# Schematics.net
KiCad netlist of a schematic drawn in EAGLE
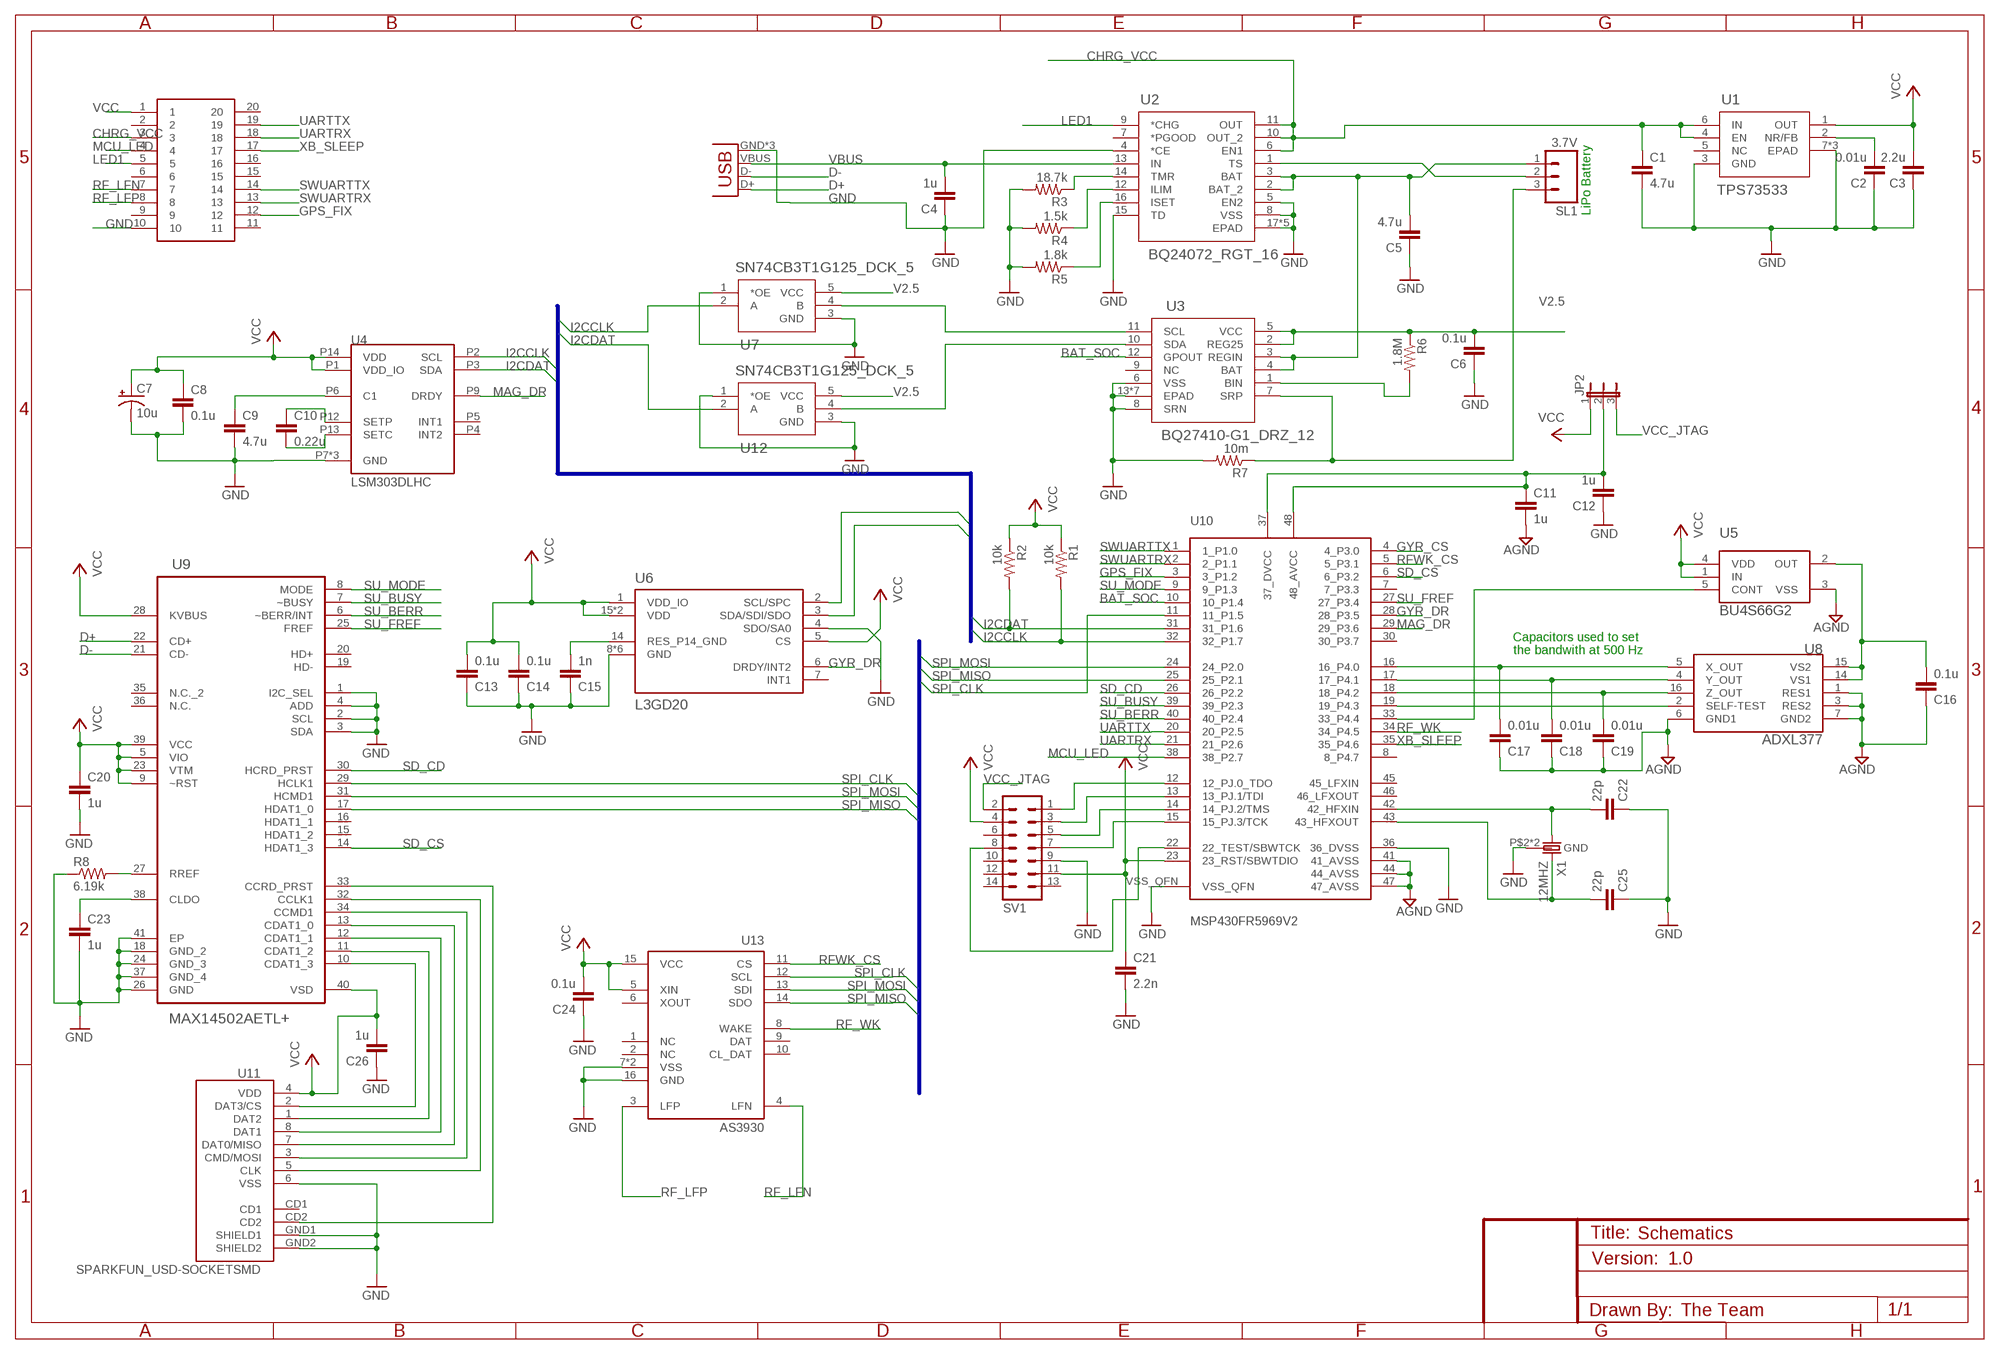
[diagram p0: schematic, sheet 1]

(export (version "E")
  (design (tool "Eeschema 10.0.6"))
  (components
    (comp (ref "C1")
      (value "4.7u")
      (footprint "eagle-import:C0603")
      (libsource (lib "eagle-import") (part "C-EUC0603"))
    )
    (comp (ref "C2")
      (value "0.01u")
      (footprint "eagle-import:C0603")
      (libsource (lib "eagle-import") (part "C-EUC0603"))
    )
    (comp (ref "C3")
      (value "2.2u")
      (footprint "eagle-import:C0603")
      (libsource (lib "eagle-import") (part "C-EUC0603"))
    )
    (comp (ref "C4")
      (value "1u")
      (footprint "eagle-import:C0603")
      (libsource (lib "eagle-import") (part "C-EUC0603"))
    )
    (comp (ref "C5")
      (value "4.7u")
      (footprint "eagle-import:C0603")
      (libsource (lib "eagle-import") (part "C-EUC0603"))
    )
    (comp (ref "C6")
      (value "0.1u")
      (footprint "eagle-import:C0603")
      (libsource (lib "eagle-import") (part "C-EUC0603"))
    )
    (comp (ref "C7")
      (value "10u")
      (footprint "eagle-import:ELECTROLYTIC_CAP")
      (libsource (lib "eagle-import") (part "SMD-AL-CAP"))
    )
    (comp (ref "C8")
      (value "0.1u")
      (footprint "eagle-import:C0603")
      (libsource (lib "eagle-import") (part "C-EUC0603"))
    )
    (comp (ref "C9")
      (value "4.7u")
      (footprint "eagle-import:C0603")
      (libsource (lib "eagle-import") (part "C-EUC0603"))
    )
    (comp (ref "C10")
      (value "0.22u")
      (footprint "eagle-import:C0603")
      (libsource (lib "eagle-import") (part "C-EUC0603"))
    )
    (comp (ref "C11")
      (value "1u")
      (footprint "eagle-import:C0603")
      (libsource (lib "eagle-import") (part "C-EUC0603"))
    )
    (comp (ref "C12")
      (value "1u")
      (footprint "eagle-import:C0603")
      (libsource (lib "eagle-import") (part "C-EUC0603"))
    )
    (comp (ref "C13")
      (value "0.1u")
      (footprint "eagle-import:C0603")
      (libsource (lib "eagle-import") (part "C-EUC0603"))
    )
    (comp (ref "C14")
      (value "0.1u")
      (footprint "eagle-import:C0603")
      (libsource (lib "eagle-import") (part "C-EUC0603"))
    )
    (comp (ref "C15")
      (value "1n")
      (footprint "eagle-import:C0603")
      (libsource (lib "eagle-import") (part "C-EUC0603"))
    )
    (comp (ref "C16")
      (value "0.1u")
      (footprint "eagle-import:C0603")
      (libsource (lib "eagle-import") (part "C-EUC0603"))
    )
    (comp (ref "C17")
      (value "0.01u")
      (footprint "eagle-import:C0603")
      (libsource (lib "eagle-import") (part "C-EUC0603"))
    )
    (comp (ref "C18")
      (value "0.01u")
      (footprint "eagle-import:C0603")
      (libsource (lib "eagle-import") (part "C-EUC0603"))
    )
    (comp (ref "C19")
      (value "0.01u")
      (footprint "eagle-import:C0603")
      (libsource (lib "eagle-import") (part "C-EUC0603"))
    )
    (comp (ref "C20")
      (value "1u")
      (footprint "eagle-import:C0603")
      (libsource (lib "eagle-import") (part "C-EUC0603"))
    )
    (comp (ref "C21")
      (value "2.2n")
      (footprint "eagle-import:C0603")
      (libsource (lib "eagle-import") (part "C-EUC0603"))
    )
    (comp (ref "C22")
      (value "22p")
      (footprint "eagle-import:C0603")
      (libsource (lib "eagle-import") (part "C-EUC0603"))
    )
    (comp (ref "C23")
      (value "1u")
      (footprint "eagle-import:C0603")
      (libsource (lib "eagle-import") (part "C-EUC0603"))
    )
    (comp (ref "C24")
      (value "0.1u")
      (footprint "eagle-import:C0603")
      (libsource (lib "eagle-import") (part "C-EUC0603"))
    )
    (comp (ref "C25")
      (value "22p")
      (footprint "eagle-import:C0603")
      (libsource (lib "eagle-import") (part "C-EUC0603"))
    )
    (comp (ref "C26")
      (value "1u")
      (footprint "eagle-import:C0603")
      (libsource (lib "eagle-import") (part "C-EUC0603"))
    )
    (comp (ref "JP1")
      (value "USB-MICROB")
      (footprint "eagle-import:USB-MICROB")
      (libsource (lib "eagle-import") (part "USB-MICROB"))
    )
    (comp (ref "JP2")
      (value "JP2E")
      (footprint "eagle-import:JP2")
      (libsource (lib "eagle-import") (part "JP2E"))
    )
    (comp (ref "JP3")
      (value "20-SOCKET")
      (footprint "eagle-import:20-SOCKET")
      (libsource (lib "eagle-import") (part "20-SOCKET"))
    )
    (comp (ref "R1")
      (value "10k")
      (footprint "eagle-import:R0603")
      (libsource (lib "eagle-import") (part "R-US_R0603"))
    )
    (comp (ref "R2")
      (value "10k")
      (footprint "eagle-import:R0603")
      (libsource (lib "eagle-import") (part "R-US_R0603"))
    )
    (comp (ref "R3")
      (value "18.7k")
      (footprint "eagle-import:R0603")
      (libsource (lib "eagle-import") (part "R-US_R0603"))
    )
    (comp (ref "R4")
      (value "1.5k")
      (footprint "eagle-import:R0603")
      (libsource (lib "eagle-import") (part "R-US_R0603"))
    )
    (comp (ref "R5")
      (value "1.8k")
      (footprint "eagle-import:R0603")
      (libsource (lib "eagle-import") (part "R-US_R0603"))
    )
    (comp (ref "R6")
      (value "1.8M")
      (footprint "eagle-import:R0603")
      (libsource (lib "eagle-import") (part "R-US_R0603"))
    )
    (comp (ref "R7")
      (value "10m")
      (footprint "eagle-import:R0603")
      (libsource (lib "eagle-import") (part "R-US_R0603"))
    )
    (comp (ref "R8")
      (value "6.19k")
      (footprint "eagle-import:R0603")
      (libsource (lib "eagle-import") (part "R-US_R0603"))
    )
    (comp (ref "SL1")
      (value "3.7V")
      (footprint "eagle-import:03P")
      (libsource (lib "eagle-import") (part "M03"))
    )
    (comp (ref "SV1")
      (value "ML14")
      (footprint "eagle-import:ML14")
      (libsource (lib "eagle-import") (part "ML14"))
    )
    (comp (ref "U1")
      (value "TPS73533")
      (footprint "eagle-import:DRV6_1P6X1")
      (fields
        (field (name "MANUFACTURER") "Texas Instruments")
        (field (name "MANUFACTURER_PART_NUMBER") "tps73533_drv_6")
      )
      (libsource (lib "eagle-import") (part "TPS73533_DRV_6"))
    )
    (comp (ref "U2")
      (value "BQ24072_RGT_16")
      (footprint "eagle-import:RGT16_1P7X1P7")
      (fields
        (field (name "GENERIC_PART_NUMBER") "BQ24072")
        (field (name "MANUFACTURER") "Texas Instruments")
      )
      (libsource (lib "eagle-import") (part "BQ24072_RGT_16"))
    )
    (comp (ref "U3")
      (value "BQ27410-G1_DRZ_12")
      (footprint "eagle-import:DRZ12_1P95X2P45")
      (fields
        (field (name "GENERIC_PART_NUMBER") "BQ27410-G1")
        (field (name "MANUFACTURER") "Texas Instruments")
      )
      (libsource (lib "eagle-import") (part "BQ27410-G1_DRZ_12"))
    )
    (comp (ref "U4")
      (value "LSM303DLHC")
      (footprint "eagle-import:LGA_3X5X1_14L")
      (libsource (lib "eagle-import") (part "LSM303DLHC"))
    )
    (comp (ref "U5")
      (value "BU4S66G2")
      (footprint "eagle-import:SSOP5")
      (libsource (lib "eagle-import") (part "BU4S66G2"))
    )
    (comp (ref "U6")
      (value "L3GD20")
      (footprint "eagle-import:L3GD20")
      (libsource (lib "eagle-import") (part "L3GD20"))
    )
    (comp (ref "U7")
      (value "SN74CB3T1G125_DCK_5")
      (footprint "eagle-import:DCK5")
      (fields
        (field (name "GENERIC_PART_NUMBER") "SN74CB3T1G125")
        (field (name "MANUFACTURER") "Texas Instruments")
        (field (name "MANUFACTURER_PART_NUMBER") "sn74cb3t1g125_dck_5")
      )
      (libsource (lib "eagle-import") (part "SN74CB3T1G125_DCK_5"))
    )
    (comp (ref "U8")
      (value "ADXL377")
      (footprint "eagle-import:LFCSP-16")
      (libsource (lib "eagle-import") (part "ADXL377"))
    )
    (comp (ref "U9")
      (value "MAX14502AETL+")
      (footprint "eagle-import:QFN40P500X500X80-41N")
      (libsource (lib "eagle-import") (part "MAX14502AETL+"))
    )
    (comp (ref "U10")
      (value "MSP430FR5969V2")
      (footprint "eagle-import:RGZ(S-PVQFN-N48)")
      (libsource (lib "eagle-import") (part "MSP430FR5969V2"))
    )
    (comp (ref "U11")
      (value "SPARKFUN_USD-SOCKETSMD")
      (footprint "eagle-import:SPARKFUN_MICRO-SD-SOCKET-PP")
      (libsource (lib "eagle-import") (part "SPARKFUN_USD-SOCKETSMD"))
    )
    (comp (ref "U12")
      (value "SN74CB3T1G125_DCK_5")
      (footprint "eagle-import:DCK5")
      (fields
        (field (name "GENERIC_PART_NUMBER") "SN74CB3T1G125")
        (field (name "MANUFACTURER") "Texas Instruments")
        (field (name "MANUFACTURER_PART_NUMBER") "sn74cb3t1g125_dck_5")
      )
      (libsource (lib "eagle-import") (part "SN74CB3T1G125_DCK_5"))
    )
    (comp (ref "U13")
      (value "AS3930")
      (footprint "eagle-import:AS3930")
      (libsource (lib "eagle-import") (part "AS3930"))
    )
    (comp (ref "X1")
      (value "12MHZ")
      (footprint "eagle-import:12MHZ")
      (libsource (lib "eagle-import") (part "12MHZ"))
    )
  )
  (nets
    (net (code "1") (name "/BAT_SOC") (class "Default")
      (node (ref "U10") (pin "10") (pinfunction "10_P1.4_10") (pintype "bidirectional"))
      (node (ref "U3") (pin "12") (pinfunction "GPOUT_12") (pintype "output"))
    )
    (net (code "2") (name "/CHRG_VCC") (class "Default")
      (node (ref "C1") (pin "1") (pinfunction "1_1") (pintype "passive"))
      (node (ref "JP3") (pin "3") (pinfunction "3_3") (pintype "bidirectional"))
      (node (ref "U1") (pin "4") (pinfunction "EN_4") (pintype "passive"))
      (node (ref "U1") (pin "6") (pinfunction "IN_6") (pintype "input"))
      (node (ref "U2") (pin "10") (pinfunction "OUT_2_10") (pintype "output"))
      (node (ref "U2") (pin "11") (pinfunction "OUT_11") (pintype "output"))
      (node (ref "U2") (pin "6") (pinfunction "EN1_6") (pintype "input"))
    )
    (net (code "3") (name "/D+") (class "Default")
      (node (ref "JP1") (pin "D+") (pinfunction "D+_D+") (pintype "bidirectional"))
      (node (ref "U9") (pin "22") (pinfunction "CD+_22") (pintype "passive"))
    )
    (net (code "4") (name "/D-") (class "Default")
      (node (ref "JP1") (pin "D-") (pinfunction "D-_D-") (pintype "bidirectional"))
      (node (ref "U9") (pin "21") (pinfunction "CD-_21") (pintype "passive"))
    )
    (net (code "5") (name "/GPS_FIX") (class "Default")
      (node (ref "JP3") (pin "12") (pinfunction "12_12") (pintype "bidirectional"))
      (node (ref "U10") (pin "3") (pinfunction "3_P1.2_3") (pintype "bidirectional"))
    )
    (net (code "6") (name "/GYR_CS") (class "Default")
      (node (ref "U10") (pin "4") (pinfunction "4_P3.0_4") (pintype "bidirectional"))
    )
    (net (code "7") (name "/GYR_DR") (class "Default")
      (node (ref "U10") (pin "28") (pinfunction "28_P3.5_28") (pintype "bidirectional"))
      (node (ref "U6") (pin "6") (pinfunction "DRDY/INT2_6") (pintype "output"))
    )
    (net (code "8") (name "/I2CCLK") (class "Default")
      (node (ref "R1") (pin "2") (pinfunction "2_2") (pintype "passive"))
      (node (ref "U10") (pin "32") (pinfunction "32_P1.7_32") (pintype "bidirectional"))
      (node (ref "U4") (pin "P2") (pinfunction "SCL_P2") (pintype "bidirectional"))
      (node (ref "U6") (pin "2") (pinfunction "SCL/SPC_2") (pintype "input"))
      (node (ref "U7") (pin "2") (pinfunction "A_2") (pintype "input"))
    )
    (net (code "9") (name "/I2CDAT") (class "Default")
      (node (ref "R2") (pin "2") (pinfunction "2_2") (pintype "passive"))
      (node (ref "U10") (pin "31") (pinfunction "31_P1.6_31") (pintype "bidirectional"))
      (node (ref "U12") (pin "2") (pinfunction "A_2") (pintype "input"))
      (node (ref "U4") (pin "P3") (pinfunction "SDA_P3") (pintype "bidirectional"))
      (node (ref "U6") (pin "3") (pinfunction "SDA/SDI/SDO_3") (pintype "bidirectional"))
    )
    (net (code "10") (name "/LED1") (class "Default")
      (node (ref "JP3") (pin "5") (pinfunction "5_5") (pintype "bidirectional"))
      (node (ref "U2") (pin "9") (pinfunction "*CHG_9") (pintype "output"))
    )
    (net (code "11") (name "/MAG_DR") (class "Default")
      (node (ref "U10") (pin "29") (pinfunction "29_P3.6_29") (pintype "bidirectional"))
      (node (ref "U4") (pin "P9") (pinfunction "DRDY_P9") (pintype "bidirectional"))
    )
    (net (code "12") (name "/MCU_LED") (class "Default")
      (node (ref "JP3") (pin "4") (pinfunction "4_4") (pintype "bidirectional"))
      (node (ref "U10") (pin "38") (pinfunction "38_P2.7_38") (pintype "bidirectional"))
    )
    (net (code "13") (name "/RFWK_CS") (class "Default")
      (node (ref "U10") (pin "5") (pinfunction "5_P3.1_5") (pintype "bidirectional"))
      (node (ref "U13") (pin "11") (pinfunction "CS_11") (pintype "bidirectional"))
    )
    (net (code "14") (name "/RF_LFN") (class "Default")
      (node (ref "JP3") (pin "7") (pinfunction "7_7") (pintype "bidirectional"))
      (node (ref "U13") (pin "4") (pinfunction "LFN_4") (pintype "bidirectional"))
    )
    (net (code "15") (name "/RF_LFP") (class "Default")
      (node (ref "JP3") (pin "8") (pinfunction "8_8") (pintype "bidirectional"))
      (node (ref "U13") (pin "3") (pinfunction "LFP_3") (pintype "bidirectional"))
    )
    (net (code "16") (name "/RF_WK") (class "Default")
      (node (ref "U10") (pin "34") (pinfunction "34_P4.5_34") (pintype "bidirectional"))
      (node (ref "U13") (pin "8") (pinfunction "WAKE_8") (pintype "bidirectional"))
    )
    (net (code "17") (name "/SD_CD") (class "Default")
      (node (ref "U10") (pin "26") (pinfunction "26_P2.2_26") (pintype "bidirectional"))
      (node (ref "U9") (pin "30") (pinfunction "HCRD_PRST_30") (pintype "passive"))
    )
    (net (code "18") (name "/SD_CS") (class "Default")
      (node (ref "U10") (pin "6") (pinfunction "6_P3.2_6") (pintype "bidirectional"))
      (node (ref "U9") (pin "14") (pinfunction "HDAT1_3_14") (pintype "passive"))
    )
    (net (code "19") (name "/SPI_CLK") (class "Default")
      (node (ref "U10") (pin "11") (pinfunction "11_P1.5_11") (pintype "bidirectional"))
      (node (ref "U13") (pin "12") (pinfunction "SCL_12") (pintype "bidirectional"))
      (node (ref "U9") (pin "29") (pinfunction "HCLK1_29") (pintype "input"))
    )
    (net (code "20") (name "/SPI_MISO") (class "Default")
      (node (ref "U10") (pin "25") (pinfunction "25_P2.1_25") (pintype "bidirectional"))
      (node (ref "U13") (pin "14") (pinfunction "SDO_14") (pintype "bidirectional"))
      (node (ref "U9") (pin "17") (pinfunction "HDAT1_0_17") (pintype "passive"))
    )
    (net (code "21") (name "/SPI_MOSI") (class "Default")
      (node (ref "U10") (pin "24") (pinfunction "24_P2.0_24") (pintype "bidirectional"))
      (node (ref "U13") (pin "13") (pinfunction "SDI_13") (pintype "bidirectional"))
      (node (ref "U9") (pin "31") (pinfunction "HCMD1_31") (pintype "passive"))
    )
    (net (code "22") (name "/SU_BERR") (class "Default")
      (node (ref "U10") (pin "40") (pinfunction "40_P2.4_40") (pintype "bidirectional"))
      (node (ref "U9") (pin "6") (pinfunction "~{BERR/INT}_6") (pintype "bidirectional"))
    )
    (net (code "23") (name "/SU_BUSY") (class "Default")
      (node (ref "U10") (pin "39") (pinfunction "39_P2.3_39") (pintype "bidirectional"))
      (node (ref "U9") (pin "7") (pinfunction "~{BUSY}_7") (pintype "output"))
    )
    (net (code "24") (name "/SU_FREF") (class "Default")
      (node (ref "U10") (pin "27") (pinfunction "27_P3.4_27") (pintype "bidirectional"))
      (node (ref "U9") (pin "25") (pinfunction "FREF_25") (pintype "passive"))
    )
    (net (code "25") (name "/SU_MODE") (class "Default")
      (node (ref "U10") (pin "9") (pinfunction "9_P1.3_9") (pintype "bidirectional"))
      (node (ref "U9") (pin "8") (pinfunction "MODE_8") (pintype "input"))
    )
    (net (code "26") (name "/SWUARTRX") (class "Default")
      (node (ref "JP3") (pin "13") (pinfunction "13_13") (pintype "bidirectional"))
      (node (ref "U10") (pin "2") (pinfunction "2_P1.1_2") (pintype "bidirectional"))
    )
    (net (code "27") (name "/SWUARTTX") (class "Default")
      (node (ref "JP3") (pin "14") (pinfunction "14_14") (pintype "bidirectional"))
      (node (ref "U10") (pin "1") (pinfunction "1_P1.0_1") (pintype "bidirectional"))
    )
    (net (code "28") (name "/UARTRX") (class "Default")
      (node (ref "JP3") (pin "18") (pinfunction "18_18") (pintype "bidirectional"))
      (node (ref "U10") (pin "21") (pinfunction "21_P2.6_21") (pintype "bidirectional"))
    )
    (net (code "29") (name "/UARTTX") (class "Default")
      (node (ref "JP3") (pin "19") (pinfunction "19_19") (pintype "bidirectional"))
      (node (ref "U10") (pin "20") (pinfunction "20_P2.5_20") (pintype "bidirectional"))
    )
    (net (code "30") (name "/V2.5") (class "Default")
      (node (ref "C6") (pin "2") (pinfunction "2_2") (pintype "passive"))
      (node (ref "R6") (pin "1") (pinfunction "1_1") (pintype "passive"))
      (node (ref "U12") (pin "5") (pinfunction "VCC_5") (pintype "power_in"))
      (node (ref "U3") (pin "2") (pinfunction "REG25_2") (pintype "power_in"))
      (node (ref "U3") (pin "5") (pinfunction "VCC_5") (pintype "power_in"))
      (node (ref "U7") (pin "5") (pinfunction "VCC_5") (pintype "power_in"))
    )
    (net (code "31") (name "/VBUS") (class "Default")
      (node (ref "C4") (pin "2") (pinfunction "2_2") (pintype "passive"))
      (node (ref "JP1") (pin "VBUS") (pinfunction "VBUS_VBUS") (pintype "bidirectional"))
      (node (ref "U2") (pin "13") (pinfunction "IN_13") (pintype "input"))
    )
    (net (code "32") (name "/VCC_JTAG") (class "Default")
      (node (ref "JP2") (pin "3") (pinfunction "3_3") (pintype "passive"))
      (node (ref "SV1") (pin "2") (pinfunction "2_2") (pintype "passive"))
    )
    (net (code "33") (name "/XB_SLEEP") (class "Default")
      (node (ref "JP3") (pin "17") (pinfunction "17_17") (pintype "bidirectional"))
      (node (ref "U10") (pin "35") (pinfunction "35_P4.6_35") (pintype "bidirectional"))
    )
    (net (code "34") (name "AGND") (class "Default")
      (node (ref "C11") (pin "2") (pinfunction "2_2") (pintype "passive"))
      (node (ref "C16") (pin "1") (pinfunction "1_1") (pintype "passive"))
      (node (ref "C17") (pin "1") (pinfunction "1_1") (pintype "passive"))
      (node (ref "C18") (pin "1") (pinfunction "1_1") (pintype "passive"))
      (node (ref "C19") (pin "1") (pinfunction "1_1") (pintype "passive"))
      (node (ref "U10") (pin "41") (pinfunction "41_AVSS_41") (pintype "bidirectional"))
      (node (ref "U10") (pin "44") (pinfunction "44_AVSS_44") (pintype "bidirectional"))
      (node (ref "U10") (pin "47") (pinfunction "47_AVSS_47") (pintype "bidirectional"))
      (node (ref "U5") (pin "3") (pinfunction "VSS_3") (pintype "bidirectional"))
      (node (ref "U8") (pin "1") (pinfunction "RES1_1") (pintype "bidirectional"))
      (node (ref "U8") (pin "3") (pinfunction "RES2_3") (pintype "bidirectional"))
      (node (ref "U8") (pin "6") (pinfunction "GND1_6") (pintype "bidirectional"))
      (node (ref "U8") (pin "7") (pinfunction "GND2_7") (pintype "bidirectional"))
    )
    (net (code "35") (name "GND") (class "Default")
      (node (ref "C1") (pin "2") (pinfunction "2_2") (pintype "passive"))
      (node (ref "C12") (pin "1") (pinfunction "1_1") (pintype "passive"))
      (node (ref "C13") (pin "1") (pinfunction "1_1") (pintype "passive"))
      (node (ref "C14") (pin "1") (pinfunction "1_1") (pintype "passive"))
      (node (ref "C15") (pin "1") (pinfunction "1_1") (pintype "passive"))
      (node (ref "C2") (pin "1") (pinfunction "1_1") (pintype "passive"))
      (node (ref "C20") (pin "2") (pinfunction "2_2") (pintype "passive"))
      (node (ref "C21") (pin "2") (pinfunction "2_2") (pintype "passive"))
      (node (ref "C22") (pin "1") (pinfunction "1_1") (pintype "passive"))
      (node (ref "C23") (pin "2") (pinfunction "2_2") (pintype "passive"))
      (node (ref "C24") (pin "1") (pinfunction "1_1") (pintype "passive"))
      (node (ref "C25") (pin "1") (pinfunction "1_1") (pintype "passive"))
      (node (ref "C26") (pin "1") (pinfunction "1_1") (pintype "passive"))
      (node (ref "C3") (pin "1") (pinfunction "1_1") (pintype "passive"))
      (node (ref "C4") (pin "1") (pinfunction "1_1") (pintype "passive"))
      (node (ref "C5") (pin "1") (pinfunction "1_1") (pintype "passive"))
      (node (ref "C6") (pin "1") (pinfunction "1_1") (pintype "passive"))
      (node (ref "C7") (pin "-") (pinfunction "-_-") (pintype "passive"))
      (node (ref "C8") (pin "2") (pinfunction "2_2") (pintype "passive"))
      (node (ref "C9") (pin "2") (pinfunction "2_2") (pintype "passive"))
      (node (ref "JP1") (pin "GND") (pinfunction "GND_GND") (pintype "bidirectional"))
      (node (ref "JP1") (pin "MT1") (pinfunction "GND_MT1") (pintype "bidirectional"))
      (node (ref "JP1") (pin "MT2") (pinfunction "GND_MT2") (pintype "bidirectional"))
      (node (ref "JP3") (pin "10") (pinfunction "10_10") (pintype "bidirectional"))
      (node (ref "R3") (pin "2") (pinfunction "2_2") (pintype "passive"))
      (node (ref "R4") (pin "2") (pinfunction "2_2") (pintype "passive"))
      (node (ref "R5") (pin "2") (pinfunction "2_2") (pintype "passive"))
      (node (ref "R7") (pin "2") (pinfunction "2_2") (pintype "passive"))
      (node (ref "R8") (pin "1") (pinfunction "1_1") (pintype "passive"))
      (node (ref "SV1") (pin "9") (pinfunction "9_9") (pintype "passive"))
      (node (ref "U1") (pin "3") (pinfunction "GND_3") (pintype "power_in"))
      (node (ref "U1") (pin "7") (pinfunction "EPAD_7") (pintype "passive"))
      (node (ref "U1") (pin "V") (pinfunction "EPAD_V") (pintype "passive"))
      (node (ref "U1") (pin "V_2") (pinfunction "EPAD_V_2") (pintype "passive"))
      (node (ref "U10") (pin "36") (pinfunction "36_DVSS_36") (pintype "bidirectional"))
      (node (ref "U10") (pin "VSS_QFN") (pinfunction "VSS_QFN_VSS_QFN") (pintype "bidirectional"))
      (node (ref "U11") (pin "6") (pinfunction "VSS_6") (pintype "bidirectional"))
      (node (ref "U11") (pin "GND1") (pinfunction "SHIELD1_GND1") (pintype "bidirectional"))
      (node (ref "U11") (pin "GND2") (pinfunction "SHIELD2_GND2") (pintype "bidirectional"))
      (node (ref "U12") (pin "1") (pinfunction "*OE_1") (pintype "input"))
      (node (ref "U12") (pin "3") (pinfunction "GND_3") (pintype "power_in"))
      (node (ref "U13") (pin "16") (pinfunction "GND_16") (pintype "bidirectional"))
      (node (ref "U13") (pin "7") (pinfunction "VSS_7") (pintype "bidirectional"))
      (node (ref "U13") (pin "EXP") (pinfunction "VSS_EXP") (pintype "bidirectional"))
      (node (ref "U2") (pin "15") (pinfunction "TD_15") (pintype "input"))
      (node (ref "U2") (pin "17") (pinfunction "EPAD_17") (pintype "power_in"))
      (node (ref "U2") (pin "4") (pinfunction "*CE_4") (pintype "input"))
      (node (ref "U2") (pin "5") (pinfunction "EN2_5") (pintype "input"))
      (node (ref "U2") (pin "8") (pinfunction "VSS_8") (pintype "power_in"))
      (node (ref "U2") (pin "V") (pinfunction "EPAD_V") (pintype "power_in"))
      (node (ref "U2") (pin "V_2") (pinfunction "EPAD_V_2") (pintype "power_in"))
      (node (ref "U2") (pin "V_3") (pinfunction "EPAD_V_3") (pintype "power_in"))
      (node (ref "U2") (pin "V_4") (pinfunction "EPAD_V_4") (pintype "power_in"))
      (node (ref "U3") (pin "13") (pinfunction "EPAD_13") (pintype "power_in"))
      (node (ref "U3") (pin "6") (pinfunction "VSS_6") (pintype "power_in"))
      (node (ref "U3") (pin "8") (pinfunction "SRN_8") (pintype "input"))
      (node (ref "U3") (pin "V") (pinfunction "EPAD_V") (pintype "power_in"))
      (node (ref "U3") (pin "V_2") (pinfunction "EPAD_V_2") (pintype "power_in"))
      (node (ref "U3") (pin "V_3") (pinfunction "EPAD_V_3") (pintype "power_in"))
      (node (ref "U3") (pin "V_4") (pinfunction "EPAD_V_4") (pintype "power_in"))
      (node (ref "U3") (pin "V_5") (pinfunction "EPAD_V_5") (pintype "power_in"))
      (node (ref "U3") (pin "V_6") (pinfunction "EPAD_V_6") (pintype "power_in"))
      (node (ref "U4") (pin "P10") (pinfunction "GND_P10") (pintype "bidirectional"))
      (node (ref "U4") (pin "P11") (pinfunction "GND_P11") (pintype "bidirectional"))
      (node (ref "U4") (pin "P7") (pinfunction "GND_P7") (pintype "bidirectional"))
      (node (ref "U6") (pin "10") (pinfunction "GND_10") (pintype "bidirectional"))
      (node (ref "U6") (pin "11") (pinfunction "GND_11") (pintype "bidirectional"))
      (node (ref "U6") (pin "12") (pinfunction "GND_12") (pintype "bidirectional"))
      (node (ref "U6") (pin "13") (pinfunction "GND_13") (pintype "bidirectional"))
      (node (ref "U6") (pin "4") (pinfunction "SDO/SA0_4") (pintype "bidirectional"))
      (node (ref "U6") (pin "8") (pinfunction "GND_8") (pintype "bidirectional"))
      (node (ref "U6") (pin "9") (pinfunction "GND_9") (pintype "bidirectional"))
      (node (ref "U7") (pin "1") (pinfunction "*OE_1") (pintype "input"))
      (node (ref "U7") (pin "3") (pinfunction "GND_3") (pintype "power_in"))
      (node (ref "U9") (pin "1") (pinfunction "I2C_SEL_1") (pintype "input"))
      (node (ref "U9") (pin "18") (pinfunction "GND_2_18") (pintype "passive"))
      (node (ref "U9") (pin "2") (pinfunction "SCL_2") (pintype "input"))
      (node (ref "U9") (pin "24") (pinfunction "GND_3_24") (pintype "passive"))
      (node (ref "U9") (pin "26") (pinfunction "GND_26") (pintype "passive"))
      (node (ref "U9") (pin "3") (pinfunction "SDA_3") (pintype "bidirectional"))
      (node (ref "U9") (pin "37") (pinfunction "GND_4_37") (pintype "passive"))
      (node (ref "U9") (pin "4") (pinfunction "ADD_4") (pintype "input"))
      (node (ref "U9") (pin "41") (pinfunction "EP_41") (pintype "passive"))
      (node (ref "X1") (pin "P$2") (pinfunction "GND_P$2") (pintype "bidirectional"))
      (node (ref "X1") (pin "P$4") (pinfunction "GND_P$4") (pintype "bidirectional"))
    )
    (net (code "36") (name "Net-(U1-NR{slash}FB)") (class "Default")
      (node (ref "C2") (pin "2") (pinfunction "2_2") (pintype "passive"))
      (node (ref "U1") (pin "2") (pinfunction "NR/FB_2") (pintype "bidirectional"))
    )
    (net (code "37") (name "Net-(U2-BAT)") (class "Default")
      (node (ref "C5") (pin "2") (pinfunction "2_2") (pintype "passive"))
      (node (ref "SL1") (pin "1") (pinfunction "1_1") (pintype "passive"))
      (node (ref "U2") (pin "2") (pinfunction "BAT_2_2") (pintype "bidirectional"))
      (node (ref "U2") (pin "3") (pinfunction "BAT_3") (pintype "bidirectional"))
      (node (ref "U3") (pin "3") (pinfunction "REGIN_3") (pintype "power_in"))
      (node (ref "U3") (pin "4") (pinfunction "BAT_4") (pintype "input"))
    )
    (net (code "38") (name "Net-(U2-ILIM)") (class "Default")
      (node (ref "R4") (pin "1") (pinfunction "1_1") (pintype "passive"))
      (node (ref "U2") (pin "12") (pinfunction "ILIM_12") (pintype "input"))
    )
    (net (code "39") (name "Net-(U2-ISET)") (class "Default")
      (node (ref "R5") (pin "1") (pinfunction "1_1") (pintype "passive"))
      (node (ref "U2") (pin "16") (pinfunction "ISET_16") (pintype "bidirectional"))
    )
    (net (code "40") (name "Net-(U2-TMR)") (class "Default")
      (node (ref "R3") (pin "1") (pinfunction "1_1") (pintype "passive"))
      (node (ref "U2") (pin "14") (pinfunction "TMR_14") (pintype "input"))
    )
    (net (code "41") (name "Net-(U2-TS)") (class "Default")
      (node (ref "SL1") (pin "2") (pinfunction "2_2") (pintype "passive"))
      (node (ref "U2") (pin "1") (pinfunction "TS_1") (pintype "input"))
    )
    (net (code "42") (name "Net-(U3-BIN)") (class "Default")
      (node (ref "R6") (pin "2") (pinfunction "2_2") (pintype "passive"))
      (node (ref "U3") (pin "1") (pinfunction "BIN_1") (pintype "input"))
    )
    (net (code "43") (name "Net-(U3-SCL)") (class "Default")
      (node (ref "U3") (pin "11") (pinfunction "SCL_11") (pintype "input"))
      (node (ref "U7") (pin "4") (pinfunction "B_4") (pintype "input"))
    )
    (net (code "44") (name "Net-(U3-SRP)") (class "Default")
      (node (ref "R7") (pin "1") (pinfunction "1_1") (pintype "passive"))
      (node (ref "SL1") (pin "3") (pinfunction "3_3") (pintype "passive"))
      (node (ref "U3") (pin "7") (pinfunction "SRP_7") (pintype "input"))
    )
    (net (code "45") (name "Net-(U4-C1)") (class "Default")
      (node (ref "C9") (pin "1") (pinfunction "1_1") (pintype "passive"))
      (node (ref "U4") (pin "P6") (pinfunction "C1_P6") (pintype "bidirectional"))
    )
    (net (code "46") (name "Net-(U4-SETC)") (class "Default")
      (node (ref "C10") (pin "2") (pinfunction "2_2") (pintype "passive"))
      (node (ref "U4") (pin "P13") (pinfunction "SETC_P13") (pintype "bidirectional"))
    )
    (net (code "47") (name "Net-(U4-SETP)") (class "Default")
      (node (ref "C10") (pin "1") (pinfunction "1_1") (pintype "passive"))
      (node (ref "U4") (pin "P12") (pinfunction "SETP_P12") (pintype "bidirectional"))
    )
    (net (code "48") (name "Net-(U5-OUT)") (class "Default")
      (node (ref "C16") (pin "2") (pinfunction "2_2") (pintype "passive"))
      (node (ref "U5") (pin "2") (pinfunction "OUT_2") (pintype "bidirectional"))
      (node (ref "U8") (pin "14") (pinfunction "VS1_14") (pintype "bidirectional"))
      (node (ref "U8") (pin "15") (pinfunction "VS2_15") (pintype "bidirectional"))
    )
    (net (code "49") (name "Net-(U6-RES_P14_GND)") (class "Default")
      (node (ref "C15") (pin "2") (pinfunction "2_2") (pintype "passive"))
      (node (ref "U6") (pin "14") (pinfunction "RES_P14_GND_14") (pintype "bidirectional"))
    )
    (net (code "50") (name "Net-(U9-CCRD_PRST)") (class "Default")
      (node (ref "U11") (pin "CD2") (pinfunction "CD2_CD2") (pintype "bidirectional"))
      (node (ref "U9") (pin "33") (pinfunction "CCRD_PRST_33") (pintype "passive"))
    )
    (net (code "51") (name "Net-(U9-CLDO)") (class "Default")
      (node (ref "C23") (pin "1") (pinfunction "1_1") (pintype "passive"))
      (node (ref "U9") (pin "38") (pinfunction "CLDO_38") (pintype "power_in"))
    )
    (net (code "52") (name "Net-(U9-RREF)") (class "Default")
      (node (ref "R8") (pin "2") (pinfunction "2_2") (pintype "passive"))
      (node (ref "U9") (pin "27") (pinfunction "RREF_27") (pintype "passive"))
    )
    (net (code "53") (name "Net-(U10-12_PJ.0_TDO)") (class "Default")
      (node (ref "SV1") (pin "1") (pinfunction "1_1") (pintype "passive"))
      (node (ref "U10") (pin "12") (pinfunction "12_PJ.0_TDO_12") (pintype "bidirectional"))
    )
    (net (code "54") (name "Net-(U10-13_PJ.1{slash}TDI)") (class "Default")
      (node (ref "SV1") (pin "3") (pinfunction "3_3") (pintype "passive"))
      (node (ref "U10") (pin "13") (pinfunction "13_PJ.1/TDI_13") (pintype "bidirectional"))
    )
    (net (code "55") (name "Net-(U10-14_PJ.2{slash}TMS)") (class "Default")
      (node (ref "SV1") (pin "5") (pinfunction "5_5") (pintype "passive"))
      (node (ref "U10") (pin "14") (pinfunction "14_PJ.2/TMS_14") (pintype "bidirectional"))
    )
    (net (code "56") (name "Net-(U10-15_PJ.3{slash}TCK)") (class "Default")
      (node (ref "SV1") (pin "7") (pinfunction "7_7") (pintype "passive"))
      (node (ref "U10") (pin "15") (pinfunction "15_PJ.3/TCK_15") (pintype "bidirectional"))
    )
    (net (code "57") (name "Net-(U10-16_P4.0)") (class "Default")
      (node (ref "C17") (pin "2") (pinfunction "2_2") (pintype "passive"))
      (node (ref "U10") (pin "16") (pinfunction "16_P4.0_16") (pintype "bidirectional"))
      (node (ref "U8") (pin "5") (pinfunction "X_OUT_5") (pintype "bidirectional"))
    )
    (net (code "58") (name "Net-(U10-17_P4.1)") (class "Default")
      (node (ref "C18") (pin "2") (pinfunction "2_2") (pintype "passive"))
      (node (ref "U10") (pin "17") (pinfunction "17_P4.1_17") (pintype "bidirectional"))
      (node (ref "U8") (pin "4") (pinfunction "Y_OUT_4") (pintype "bidirectional"))
    )
    (net (code "59") (name "Net-(U10-18_P4.2)") (class "Default")
      (node (ref "C19") (pin "2") (pinfunction "2_2") (pintype "passive"))
      (node (ref "U10") (pin "18") (pinfunction "18_P4.2_18") (pintype "bidirectional"))
      (node (ref "U8") (pin "16") (pinfunction "Z_OUT_16") (pintype "bidirectional"))
    )
    (net (code "60") (name "Net-(U10-19_P4.3)") (class "Default")
      (node (ref "U10") (pin "19") (pinfunction "19_P4.3_19") (pintype "bidirectional"))
      (node (ref "U8") (pin "2") (pinfunction "SELF-TEST_2") (pintype "bidirectional"))
    )
    (net (code "61") (name "Net-(U10-22_TEST{slash}SBWTCK)") (class "Default")
      (node (ref "SV1") (pin "8") (pinfunction "8_8") (pintype "passive"))
      (node (ref "U10") (pin "22") (pinfunction "22_TEST/SBWTCK_22") (pintype "bidirectional"))
    )
    (net (code "62") (name "Net-(U10-33_P4.4)") (class "Default")
      (node (ref "U10") (pin "33") (pinfunction "33_P4.4_33") (pintype "bidirectional"))
      (node (ref "U5") (pin "5") (pinfunction "CONT_5") (pintype "bidirectional"))
    )
    (net (code "63") (name "Net-(U10-37_DVCC)") (class "Default")
      (node (ref "C11") (pin "1") (pinfunction "1_1") (pintype "passive"))
      (node (ref "C12") (pin "2") (pinfunction "2_2") (pintype "passive"))
      (node (ref "JP2") (pin "2") (pinfunction "2_2") (pintype "passive"))
      (node (ref "U10") (pin "37") (pinfunction "37_DVCC_37") (pintype "bidirectional"))
      (node (ref "U10") (pin "48") (pinfunction "48_AVCC_48") (pintype "bidirectional"))
    )
    (net (code "64") (name "Net-(U10-42_HFXIN)") (class "Default")
      (node (ref "C22") (pin "2") (pinfunction "2_2") (pintype "passive"))
      (node (ref "U10") (pin "42") (pinfunction "42_HFXIN_42") (pintype "bidirectional"))
      (node (ref "X1") (pin "P$1") (pinfunction "1_P$1") (pintype "passive"))
    )
    (net (code "65") (name "Net-(U10-43_HFXOUT)") (class "Default")
      (node (ref "C25") (pin "2") (pinfunction "2_2") (pintype "passive"))
      (node (ref "U10") (pin "43") (pinfunction "43_HFXOUT_43") (pintype "bidirectional"))
      (node (ref "X1") (pin "P$3") (pinfunction "2_P$3") (pintype "passive"))
    )
    (net (code "66") (name "Net-(U11-CLK)") (class "Default")
      (node (ref "U11") (pin "5") (pinfunction "CLK_5") (pintype "bidirectional"))
      (node (ref "U9") (pin "32") (pinfunction "CCLK1_32") (pintype "input"))
    )
    (net (code "67") (name "Net-(U11-CMD{slash}MOSI)") (class "Default")
      (node (ref "U11") (pin "3") (pinfunction "CMD/MOSI_3") (pintype "bidirectional"))
      (node (ref "U9") (pin "34") (pinfunction "CCMD1_34") (pintype "passive"))
    )
    (net (code "68") (name "Net-(U11-DAT0{slash}MISO)") (class "Default")
      (node (ref "U11") (pin "7") (pinfunction "DAT0/MISO_7") (pintype "bidirectional"))
      (node (ref "U9") (pin "13") (pinfunction "CDAT1_0_13") (pintype "passive"))
    )
    (net (code "69") (name "Net-(U11-DAT1)") (class "Default")
      (node (ref "U11") (pin "8") (pinfunction "DAT1_8") (pintype "bidirectional"))
      (node (ref "U9") (pin "12") (pinfunction "CDAT1_1_12") (pintype "passive"))
    )
    (net (code "70") (name "Net-(U11-DAT2)") (class "Default")
      (node (ref "U11") (pin "1") (pinfunction "DAT2_1") (pintype "bidirectional"))
      (node (ref "U9") (pin "11") (pinfunction "CDAT1_2_11") (pintype "passive"))
    )
    (net (code "71") (name "Net-(U11-DAT3{slash}CS)") (class "Default")
      (node (ref "U11") (pin "2") (pinfunction "DAT3/CS_2") (pintype "bidirectional"))
      (node (ref "U9") (pin "10") (pinfunction "CDAT1_3_10") (pintype "passive"))
    )
    (net (code "72") (name "Net-(U12-B)") (class "Default")
      (node (ref "U12") (pin "4") (pinfunction "B_4") (pintype "input"))
      (node (ref "U3") (pin "10") (pinfunction "SDA_10") (pintype "bidirectional"))
    )
    (net (code "73") (name "VCC") (class "Default")
      (node (ref "C13") (pin "2") (pinfunction "2_2") (pintype "passive"))
      (node (ref "C14") (pin "2") (pinfunction "2_2") (pintype "passive"))
      (node (ref "C20") (pin "1") (pinfunction "1_1") (pintype "passive"))
      (node (ref "C21") (pin "1") (pinfunction "1_1") (pintype "passive"))
      (node (ref "C24") (pin "2") (pinfunction "2_2") (pintype "passive"))
      (node (ref "C26") (pin "2") (pinfunction "2_2") (pintype "passive"))
      (node (ref "C3") (pin "2") (pinfunction "2_2") (pintype "passive"))
      (node (ref "C7") (pin "+") (pinfunction "+_+") (pintype "passive"))
      (node (ref "C8") (pin "1") (pinfunction "1_1") (pintype "passive"))
      (node (ref "JP2") (pin "1") (pinfunction "1_1") (pintype "passive"))
      (node (ref "JP3") (pin "1") (pinfunction "1_1") (pintype "bidirectional"))
      (node (ref "R1") (pin "1") (pinfunction "1_1") (pintype "passive"))
      (node (ref "R2") (pin "1") (pinfunction "1_1") (pintype "passive"))
      (node (ref "SV1") (pin "11") (pinfunction "11_11") (pintype "passive"))
      (node (ref "SV1") (pin "4") (pinfunction "4_4") (pintype "passive"))
      (node (ref "U1") (pin "1") (pinfunction "OUT_1") (pintype "power_in"))
      (node (ref "U10") (pin "23") (pinfunction "23_RST/SBWTDIO_23") (pintype "bidirectional"))
      (node (ref "U11") (pin "4") (pinfunction "VDD_4") (pintype "bidirectional"))
      (node (ref "U13") (pin "15") (pinfunction "VCC_15") (pintype "bidirectional"))
      (node (ref "U13") (pin "5") (pinfunction "XIN_5") (pintype "bidirectional"))
      (node (ref "U4") (pin "P1") (pinfunction "VDD_IO_P1") (pintype "bidirectional"))
      (node (ref "U4") (pin "P14") (pinfunction "VDD_P14") (pintype "bidirectional"))
      (node (ref "U5") (pin "1") (pinfunction "IN_1") (pintype "bidirectional"))
      (node (ref "U5") (pin "4") (pinfunction "VDD_4") (pintype "bidirectional"))
      (node (ref "U6") (pin "1") (pinfunction "VDD_IO_1") (pintype "bidirectional"))
      (node (ref "U6") (pin "15") (pinfunction "VDD_15") (pintype "bidirectional"))
      (node (ref "U6") (pin "16") (pinfunction "VDD_16") (pintype "bidirectional"))
      (node (ref "U6") (pin "5") (pinfunction "CS_5") (pintype "input"))
      (node (ref "U9") (pin "23") (pinfunction "VTM_23") (pintype "passive"))
      (node (ref "U9") (pin "28") (pinfunction "KVBUS_28") (pintype "passive"))
      (node (ref "U9") (pin "39") (pinfunction "VCC_39") (pintype "power_in"))
      (node (ref "U9") (pin "40") (pinfunction "VSD_40") (pintype "power_in"))
      (node (ref "U9") (pin "5") (pinfunction "VIO_5") (pintype "passive"))
      (node (ref "U9") (pin "9") (pinfunction "~{RST}_9") (pintype "input"))
    )
    (net (code "74") (name "unconnected-(JP3-Pad2)") (class "Default")
      (node (ref "JP3") (pin "2") (pinfunction "2_2") (pintype "bidirectional"))
    )
    (net (code "75") (name "unconnected-(JP3-Pad6)") (class "Default")
      (node (ref "JP3") (pin "6") (pinfunction "6_6") (pintype "bidirectional"))
    )
    (net (code "76") (name "unconnected-(JP3-Pad9)") (class "Default")
      (node (ref "JP3") (pin "9") (pinfunction "9_9") (pintype "bidirectional"))
    )
    (net (code "77") (name "unconnected-(JP3-Pad11)") (class "Default")
      (node (ref "JP3") (pin "11") (pinfunction "11_11") (pintype "bidirectional"))
    )
    (net (code "78") (name "unconnected-(JP3-Pad15)") (class "Default")
      (node (ref "JP3") (pin "15") (pinfunction "15_15") (pintype "bidirectional"))
    )
    (net (code "79") (name "unconnected-(JP3-Pad16)") (class "Default")
      (node (ref "JP3") (pin "16") (pinfunction "16_16") (pintype "bidirectional"))
    )
    (net (code "80") (name "unconnected-(JP3-Pad20)") (class "Default")
      (node (ref "JP3") (pin "20") (pinfunction "20_20") (pintype "bidirectional"))
    )
    (net (code "81") (name "unconnected-(SV1-Pad6)") (class "Default")
      (node (ref "SV1") (pin "6") (pinfunction "6_6") (pintype "passive"))
    )
    (net (code "82") (name "unconnected-(SV1-Pad10)") (class "Default")
      (node (ref "SV1") (pin "10") (pinfunction "10_10") (pintype "passive"))
    )
    (net (code "83") (name "unconnected-(SV1-Pad12)") (class "Default")
      (node (ref "SV1") (pin "12") (pinfunction "12_12") (pintype "passive"))
    )
    (net (code "84") (name "unconnected-(SV1-Pad13)") (class "Default")
      (node (ref "SV1") (pin "13") (pinfunction "13_13") (pintype "passive"))
    )
    (net (code "85") (name "unconnected-(SV1-Pad14)") (class "Default")
      (node (ref "SV1") (pin "14") (pinfunction "14_14") (pintype "passive"))
    )
    (net (code "86") (name "unconnected-(U1-NC-Pad5)") (class "Default")
      (node (ref "U1") (pin "5") (pinfunction "NC_5") (pintype "passive"))
    )
    (net (code "87") (name "unconnected-(U2-*PGOOD-Pad7)") (class "Default")
      (node (ref "U2") (pin "7") (pinfunction "*PGOOD_7") (pintype "output"))
    )
    (net (code "88") (name "unconnected-(U3-NC-Pad9)") (class "Default")
      (node (ref "U3") (pin "9") (pinfunction "NC_9") (pintype "no_connect"))
    )
    (net (code "89") (name "unconnected-(U4-INT1-PadP5)") (class "Default")
      (node (ref "U4") (pin "P5") (pinfunction "INT1_P5") (pintype "bidirectional"))
    )
    (net (code "90") (name "unconnected-(U4-INT2-PadP4)") (class "Default")
      (node (ref "U4") (pin "P4") (pinfunction "INT2_P4") (pintype "bidirectional"))
    )
    (net (code "91") (name "unconnected-(U6-INT1-Pad7)") (class "Default")
      (node (ref "U6") (pin "7") (pinfunction "INT1_7") (pintype "output"))
    )
    (net (code "92") (name "unconnected-(U9-HD+-Pad20)") (class "Default")
      (node (ref "U9") (pin "20") (pinfunction "HD+_20") (pintype "passive"))
    )
    (net (code "93") (name "unconnected-(U9-HD--Pad19)") (class "Default")
      (node (ref "U9") (pin "19") (pinfunction "HD-_19") (pintype "passive"))
    )
    (net (code "94") (name "unconnected-(U9-HDAT1_1-Pad16)") (class "Default")
      (node (ref "U9") (pin "16") (pinfunction "HDAT1_1_16") (pintype "passive"))
    )
    (net (code "95") (name "unconnected-(U9-HDAT1_2-Pad15)") (class "Default")
      (node (ref "U9") (pin "15") (pinfunction "HDAT1_2_15") (pintype "passive"))
    )
    (net (code "96") (name "unconnected-(U9-N.C.-Pad36)") (class "Default")
      (node (ref "U9") (pin "36") (pinfunction "N.C._36") (pintype "no_connect"))
    )
    (net (code "97") (name "unconnected-(U9-N.C._2-Pad35)") (class "Default")
      (node (ref "U9") (pin "35") (pinfunction "N.C._2_35") (pintype "no_connect"))
    )
    (net (code "98") (name "unconnected-(U10-7_P3.3-Pad7)") (class "Default")
      (node (ref "U10") (pin "7") (pinfunction "7_P3.3_7") (pintype "bidirectional"))
    )
    (net (code "99") (name "unconnected-(U10-8_P4.7-Pad8)") (class "Default")
      (node (ref "U10") (pin "8") (pinfunction "8_P4.7_8") (pintype "bidirectional"))
    )
    (net (code "100") (name "unconnected-(U10-30_P3.7-Pad30)") (class "Default")
      (node (ref "U10") (pin "30") (pinfunction "30_P3.7_30") (pintype "bidirectional"))
    )
    (net (code "101") (name "unconnected-(U10-45_LFXIN-Pad45)") (class "Default")
      (node (ref "U10") (pin "45") (pinfunction "45_LFXIN_45") (pintype "bidirectional"))
    )
    (net (code "102") (name "unconnected-(U10-46_LFXOUT-Pad46)") (class "Default")
      (node (ref "U10") (pin "46") (pinfunction "46_LFXOUT_46") (pintype "bidirectional"))
    )
    (net (code "103") (name "unconnected-(U11-PadCD1)") (class "Default")
      (node (ref "U11") (pin "CD1") (pinfunction "CD1_CD1") (pintype "bidirectional"))
    )
    (net (code "104") (name "unconnected-(U13-CL_DAT-Pad10)") (class "Default")
      (node (ref "U13") (pin "10") (pinfunction "CL_DAT_10") (pintype "bidirectional"))
    )
    (net (code "105") (name "unconnected-(U13-DAT-Pad9)") (class "Default")
      (node (ref "U13") (pin "9") (pinfunction "DAT_9") (pintype "bidirectional"))
    )
    (net (code "106") (name "unconnected-(U13-NC-Pad1)") (class "Default")
      (node (ref "U13") (pin "1") (pinfunction "NC_1") (pintype "bidirectional"))
    )
    (net (code "107") (name "unconnected-(U13-NC-Pad2)") (class "Default")
      (node (ref "U13") (pin "2") (pinfunction "NC_2") (pintype "bidirectional"))
    )
    (net (code "108") (name "unconnected-(U13-XOUT-Pad6)") (class "Default")
      (node (ref "U13") (pin "6") (pinfunction "XOUT_6") (pintype "bidirectional"))
    )
  )
)
